# go_error_forward.net
KiCad netlist of a schematic drawn in EAGLE
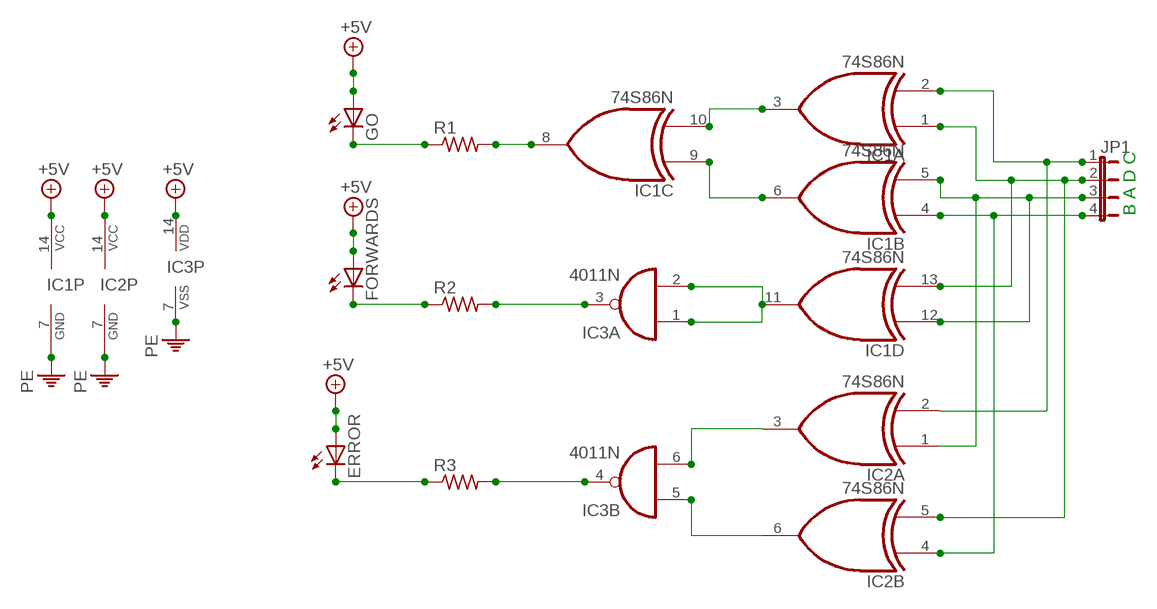
[diagram p0: schematic, sheet 1]

(export (version "E")
  (design (tool "Eeschema 10.0.6"))
  (components
    (comp (ref "ERROR")
      (value "LED5MM")
      (footprint "eagle-import:LED5MM")
      (libsource (lib "eagle-import") (part "LED5MM"))
    )
    (comp (ref "FORWARDS")
      (value "LED5MM")
      (footprint "eagle-import:LED5MM")
      (libsource (lib "eagle-import") (part "LED5MM"))
    )
    (comp (ref "GO")
      (value "LED5MM")
      (footprint "eagle-import:LED5MM")
      (libsource (lib "eagle-import") (part "LED5MM"))
    )
    (comp (ref "IC1")
      (value "74S86N")
      (footprint "eagle-import:DIL14")
      (libsource (lib "eagle-import") (part "7486NS"))
    )
    (comp (ref "IC2")
      (value "74S86N")
      (footprint "eagle-import:DIL14")
      (libsource (lib "eagle-import") (part "7486NS"))
    )
    (comp (ref "IC3")
      (value "4011N")
      (footprint "eagle-import:DIL14")
      (libsource (lib "eagle-import") (part "4011N"))
    )
    (comp (ref "JP1")
      (value "JP4E")
      (footprint "eagle-import:JP4")
      (libsource (lib "eagle-import") (part "JP4E"))
    )
    (comp (ref "R1")
      (value "R-US_0207/10")
      (footprint "eagle-import:0207_10")
      (libsource (lib "eagle-import") (part "R-US_0207/10"))
    )
    (comp (ref "R2")
      (value "R-US_0207/10")
      (footprint "eagle-import:0207_10")
      (libsource (lib "eagle-import") (part "R-US_0207/10"))
    )
    (comp (ref "R3")
      (value "R-US_0207/10")
      (footprint "eagle-import:0207_10")
      (libsource (lib "eagle-import") (part "R-US_0207/10"))
    )
  )
  (nets
    (net (code "1") (name "+5V") (class "Default")
      (node (ref "ERROR") (pin "A") (pinfunction "A_A") (pintype "passive"))
      (node (ref "FORWARDS") (pin "A") (pinfunction "A_A") (pintype "passive"))
      (node (ref "GO") (pin "A") (pinfunction "A_A") (pintype "passive"))
      (node (ref "IC1") (pin "14") (pinfunction "VCC_14") (pintype "power_in"))
      (node (ref "IC2") (pin "14") (pinfunction "VCC_14") (pintype "power_in"))
      (node (ref "IC3") (pin "14") (pinfunction "VDD_14") (pintype "power_in"))
    )
    (net (code "2") (name "Net-(ERROR-C)") (class "Default")
      (node (ref "ERROR") (pin "K") (pinfunction "C_K") (pintype "passive"))
      (node (ref "R3") (pin "1") (pinfunction "1_1") (pintype "passive"))
    )
    (net (code "3") (name "Net-(FORWARDS-C)") (class "Default")
      (node (ref "FORWARDS") (pin "K") (pinfunction "C_K") (pintype "passive"))
      (node (ref "R2") (pin "1") (pinfunction "1_1") (pintype "passive"))
    )
    (net (code "4") (name "Net-(GO-C)") (class "Default")
      (node (ref "GO") (pin "K") (pinfunction "C_K") (pintype "passive"))
      (node (ref "R1") (pin "1") (pinfunction "1_1") (pintype "passive"))
    )
    (net (code "5") (name "Net-(IC1A-I0)") (class "Default")
      (node (ref "IC1") (pin "1") (pinfunction "I0_1") (pintype "input"))
      (node (ref "IC1") (pin "13") (pinfunction "I1_13") (pintype "input"))
      (node (ref "IC2") (pin "5") (pinfunction "I1_5") (pintype "input"))
      (node (ref "JP1") (pin "2") (pinfunction "2_2") (pintype "passive"))
    )
    (net (code "6") (name "Net-(IC1A-I1)") (class "Default")
      (node (ref "IC1") (pin "2") (pinfunction "I1_2") (pintype "input"))
      (node (ref "IC2") (pin "2") (pinfunction "I1_2") (pintype "input"))
      (node (ref "JP1") (pin "1") (pinfunction "1_1") (pintype "passive"))
    )
    (net (code "7") (name "Net-(IC1A-O)") (class "Default")
      (node (ref "IC1") (pin "10") (pinfunction "I1_10") (pintype "input"))
      (node (ref "IC1") (pin "3") (pinfunction "O_3") (pintype "output"))
    )
    (net (code "8") (name "Net-(IC1B-I0)") (class "Default")
      (node (ref "IC1") (pin "4") (pinfunction "I0_4") (pintype "input"))
      (node (ref "IC2") (pin "4") (pinfunction "I0_4") (pintype "input"))
      (node (ref "JP1") (pin "4") (pinfunction "4_4") (pintype "passive"))
    )
    (net (code "9") (name "Net-(IC1B-I1)") (class "Default")
      (node (ref "IC1") (pin "12") (pinfunction "I0_12") (pintype "input"))
      (node (ref "IC1") (pin "5") (pinfunction "I1_5") (pintype "input"))
      (node (ref "IC2") (pin "1") (pinfunction "I0_1") (pintype "input"))
      (node (ref "JP1") (pin "3") (pinfunction "3_3") (pintype "passive"))
    )
    (net (code "10") (name "Net-(IC1B-O)") (class "Default")
      (node (ref "IC1") (pin "6") (pinfunction "O_6") (pintype "output"))
      (node (ref "IC1") (pin "9") (pinfunction "I0_9") (pintype "input"))
    )
    (net (code "11") (name "Net-(IC1C-O)") (class "Default")
      (node (ref "IC1") (pin "8") (pinfunction "O_8") (pintype "output"))
      (node (ref "R1") (pin "2") (pinfunction "2_2") (pintype "passive"))
    )
    (net (code "12") (name "Net-(IC1D-O)") (class "Default")
      (node (ref "IC1") (pin "11") (pinfunction "O_11") (pintype "output"))
      (node (ref "IC3") (pin "1") (pinfunction "I0_1") (pintype "input"))
      (node (ref "IC3") (pin "2") (pinfunction "I1_2") (pintype "input"))
    )
    (net (code "13") (name "Net-(IC2A-O)") (class "Default")
      (node (ref "IC2") (pin "3") (pinfunction "O_3") (pintype "output"))
      (node (ref "IC3") (pin "6") (pinfunction "I1_6") (pintype "input"))
    )
    (net (code "14") (name "Net-(IC2B-O)") (class "Default")
      (node (ref "IC2") (pin "6") (pinfunction "O_6") (pintype "output"))
      (node (ref "IC3") (pin "5") (pinfunction "I0_5") (pintype "input"))
    )
    (net (code "15") (name "Net-(IC3A-O)") (class "Default")
      (node (ref "IC3") (pin "3") (pinfunction "O_3") (pintype "output"))
      (node (ref "R2") (pin "2") (pinfunction "2_2") (pintype "passive"))
    )
    (net (code "16") (name "Net-(IC3B-O)") (class "Default")
      (node (ref "IC3") (pin "4") (pinfunction "O_4") (pintype "output"))
      (node (ref "R3") (pin "2") (pinfunction "2_2") (pintype "passive"))
    )
    (net (code "17") (name "PE") (class "Default")
      (node (ref "IC1") (pin "7") (pinfunction "GND_7") (pintype "power_in"))
      (node (ref "IC2") (pin "7") (pinfunction "GND_7") (pintype "power_in"))
      (node (ref "IC3") (pin "7") (pinfunction "VSS_7") (pintype "power_in"))
    )
  )
)
